# Power.net
KiCad netlist of a schematic drawn in Altium Designer
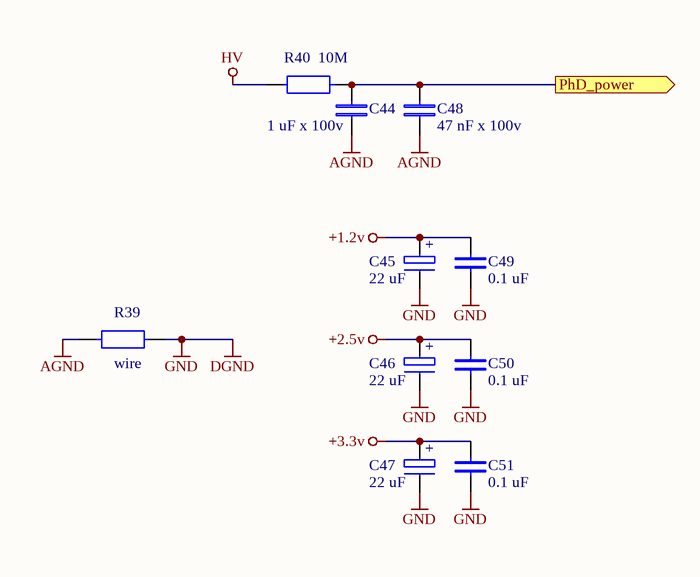
[diagram p0: Power.SchDoc]

(export (version "E")
  (design (tool "Eeschema 10.0.6"))
  (components
    (comp (ref "C44")
      (value "1 uF x 100v")
      (footprint "CAP4")
      (description "K73-17")
      (libsource (lib "*") (part "C"))
    )
    (comp (ref "C45") (value "22 uF") (footprint "CP6032") (libsource (lib "*") (part "C POL")))
    (comp (ref "C46") (value "22 uF") (footprint "CP6032") (libsource (lib "*") (part "C POL")))
    (comp (ref "C47") (value "22 uF") (footprint "CP6032") (libsource (lib "*") (part "C POL")))
    (comp (ref "C48") (value "47 nF x 100v") (footprint "1206") (libsource (lib "*") (part "C")))
    (comp (ref "C49") (value "0.1 uF") (footprint "1206") (libsource (lib "*") (part "C")))
    (comp (ref "C50") (value "0.1 uF") (footprint "1206") (libsource (lib "*") (part "C")))
    (comp (ref "C51") (value "0.1 uF") (footprint "1206") (libsource (lib "*") (part "C")))
    (comp (ref "R39") (value "wire") (footprint "1206") (libsource (lib "*") (part "R")))
    (comp (ref "R40") (value "10M") (footprint "1206") (libsource (lib "*") (part "R")))
  )
  (nets
    (net (code "1") (name "+1.2v") (class "Default")
      (node (ref "C45") (pin "+") (pinfunction "+_+") (pintype "passive"))
      (node (ref "C49") (pin "2") (pinfunction "2_2") (pintype "passive"))
    )
    (net (code "2") (name "+2.5v") (class "Default")
      (node (ref "C46") (pin "+") (pinfunction "+_+") (pintype "passive"))
      (node (ref "C50") (pin "2") (pinfunction "2_2") (pintype "passive"))
    )
    (net (code "3") (name "+3.3v") (class "Default")
      (node (ref "C47") (pin "+") (pinfunction "+_+") (pintype "passive"))
      (node (ref "C51") (pin "2") (pinfunction "2_2") (pintype "passive"))
    )
    (net (code "4") (name "/PhD_power") (class "Default")
      (node (ref "C44") (pin "2") (pinfunction "2_2") (pintype "passive"))
      (node (ref "C48") (pin "2") (pinfunction "2_2") (pintype "passive"))
      (node (ref "R40") (pin "2") (pinfunction "2_2") (pintype "passive"))
    )
    (net (code "5") (name "AGND") (class "Default")
      (node (ref "C44") (pin "1") (pinfunction "1_1") (pintype "passive"))
      (node (ref "C48") (pin "1") (pinfunction "1_1") (pintype "passive"))
      (node (ref "R39") (pin "2") (pinfunction "2_2") (pintype "passive"))
    )
    (net (code "6") (name "DGND") (class "Default")
      (node (ref "C45") (pin "-") (pinfunction "-_-") (pintype "passive"))
      (node (ref "C46") (pin "-") (pinfunction "-_-") (pintype "passive"))
      (node (ref "C47") (pin "-") (pinfunction "-_-") (pintype "passive"))
      (node (ref "C49") (pin "1") (pinfunction "1_1") (pintype "passive"))
      (node (ref "C50") (pin "1") (pinfunction "1_1") (pintype "passive"))
      (node (ref "C51") (pin "1") (pinfunction "1_1") (pintype "passive"))
      (node (ref "R39") (pin "1") (pinfunction "1_1") (pintype "passive"))
    )
    (net (code "7") (name "HV") (class "Default")
      (node (ref "R40") (pin "1") (pinfunction "1_1") (pintype "passive"))
    )
  )
)
